# DemoSensorAddon.net
KiCad netlist of a schematic drawn in EAGLE
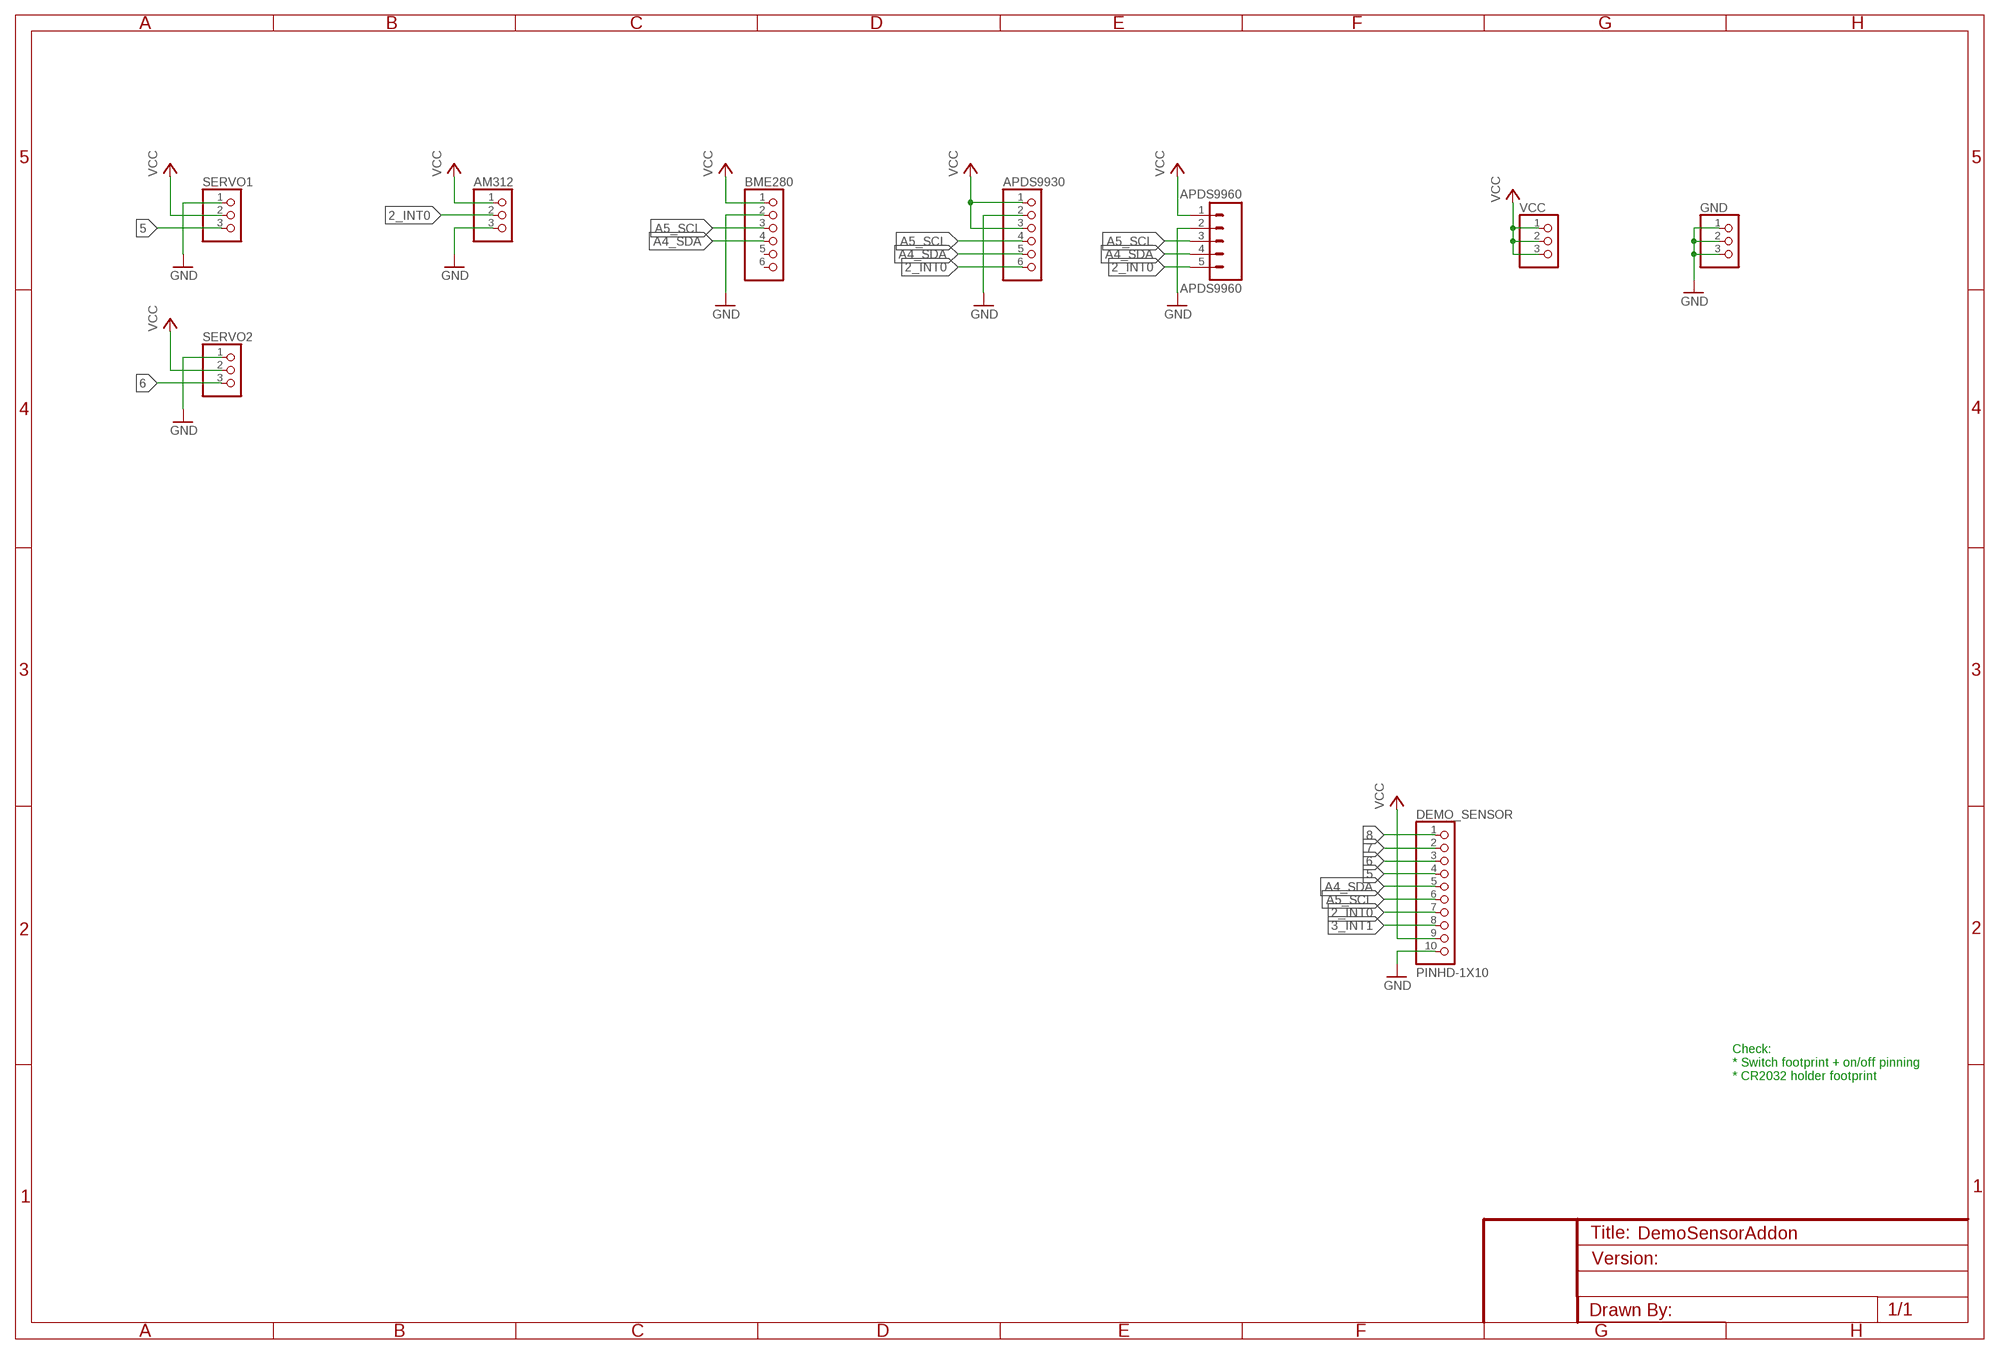
[diagram p0: schematic, sheet 1]

(export (version "E")
  (design (tool "Eeschema 10.0.6"))
  (components
    (comp (ref "AM312")
      (value "PINHD-1X3")
      (footprint "eagle-import:1X03")
      (libsource (lib "eagle-import") (part "PINHD-1X3"))
    )
    (comp (ref "APDS9930")
      (value "PINHD-1X6")
      (footprint "eagle-import:1X06")
      (libsource (lib "eagle-import") (part "PINHD-1X6"))
    )
    (comp (ref "APDS9960")
      (value "APDS9960")
      (footprint "eagle-import:1X05")
      (libsource (lib "eagle-import") (part "M05PTH"))
    )
    (comp (ref "BME280")
      (value "PINHD-1X6")
      (footprint "eagle-import:1X06")
      (libsource (lib "eagle-import") (part "PINHD-1X6"))
    )
    (comp (ref "DEMO_SENSOR")
      (value "PINHD-1X10")
      (footprint "eagle-import:1X10-BIG")
      (libsource (lib "eagle-import") (part "PINHD-1X10"))
    )
    (comp (ref "GND")
      (value "PINHD-1X3")
      (footprint "eagle-import:1X03")
      (libsource (lib "eagle-import") (part "PINHD-1X3"))
    )
    (comp (ref "SERVO1")
      (value "PINHD-1X3")
      (footprint "eagle-import:1X03")
      (libsource (lib "eagle-import") (part "PINHD-1X3"))
    )
    (comp (ref "SERVO2")
      (value "PINHD-1X3")
      (footprint "eagle-import:1X03")
      (libsource (lib "eagle-import") (part "PINHD-1X3"))
    )
    (comp (ref "VCC")
      (value "PINHD-1X3")
      (footprint "eagle-import:1X03")
      (libsource (lib "eagle-import") (part "PINHD-1X3"))
    )
  )
  (nets
    (net (code "1") (name "2_INT0") (class "Default")
      (node (ref "AM312") (pin "2") (pinfunction "2_2") (pintype "passive"))
      (node (ref "APDS9930") (pin "6") (pinfunction "6_6") (pintype "passive"))
      (node (ref "APDS9960") (pin "5") (pinfunction "5_5") (pintype "passive"))
      (node (ref "DEMO_SENSOR") (pin "7") (pinfunction "7_7") (pintype "passive"))
    )
    (net (code "2") (name "3_INT1") (class "Default")
      (node (ref "DEMO_SENSOR") (pin "8") (pinfunction "8_8") (pintype "passive"))
    )
    (net (code "3") (name "5") (class "Default")
      (node (ref "DEMO_SENSOR") (pin "4") (pinfunction "4_4") (pintype "passive"))
      (node (ref "SERVO1") (pin "3") (pinfunction "3_3") (pintype "passive"))
    )
    (net (code "4") (name "6") (class "Default")
      (node (ref "DEMO_SENSOR") (pin "3") (pinfunction "3_3") (pintype "passive"))
      (node (ref "SERVO2") (pin "3") (pinfunction "3_3") (pintype "passive"))
    )
    (net (code "5") (name "7") (class "Default")
      (node (ref "DEMO_SENSOR") (pin "2") (pinfunction "2_2") (pintype "passive"))
    )
    (net (code "6") (name "8") (class "Default")
      (node (ref "DEMO_SENSOR") (pin "1") (pinfunction "1_1") (pintype "passive"))
    )
    (net (code "7") (name "A4_SDA") (class "Default")
      (node (ref "APDS9930") (pin "5") (pinfunction "5_5") (pintype "passive"))
      (node (ref "APDS9960") (pin "4") (pinfunction "4_4") (pintype "passive"))
      (node (ref "BME280") (pin "4") (pinfunction "4_4") (pintype "passive"))
      (node (ref "DEMO_SENSOR") (pin "5") (pinfunction "5_5") (pintype "passive"))
    )
    (net (code "8") (name "A5_SCL") (class "Default")
      (node (ref "APDS9930") (pin "4") (pinfunction "4_4") (pintype "passive"))
      (node (ref "APDS9960") (pin "3") (pinfunction "3_3") (pintype "passive"))
      (node (ref "BME280") (pin "3") (pinfunction "3_3") (pintype "passive"))
      (node (ref "DEMO_SENSOR") (pin "6") (pinfunction "6_6") (pintype "passive"))
    )
    (net (code "9") (name "GND") (class "Default")
      (node (ref "AM312") (pin "3") (pinfunction "3_3") (pintype "passive"))
      (node (ref "APDS9930") (pin "2") (pinfunction "2_2") (pintype "passive"))
      (node (ref "APDS9960") (pin "2") (pinfunction "2_2") (pintype "passive"))
      (node (ref "BME280") (pin "2") (pinfunction "2_2") (pintype "passive"))
      (node (ref "DEMO_SENSOR") (pin "10") (pinfunction "10_10") (pintype "passive"))
      (node (ref "GND") (pin "1") (pinfunction "1_1") (pintype "passive"))
      (node (ref "GND") (pin "2") (pinfunction "2_2") (pintype "passive"))
      (node (ref "GND") (pin "3") (pinfunction "3_3") (pintype "passive"))
      (node (ref "SERVO1") (pin "1") (pinfunction "1_1") (pintype "passive"))
      (node (ref "SERVO2") (pin "1") (pinfunction "1_1") (pintype "passive"))
    )
    (net (code "10") (name "VCC") (class "Default")
      (node (ref "AM312") (pin "1") (pinfunction "1_1") (pintype "passive"))
      (node (ref "APDS9930") (pin "1") (pinfunction "1_1") (pintype "passive"))
      (node (ref "APDS9930") (pin "3") (pinfunction "3_3") (pintype "passive"))
      (node (ref "APDS9960") (pin "1") (pinfunction "1_1") (pintype "passive"))
      (node (ref "BME280") (pin "1") (pinfunction "1_1") (pintype "passive"))
      (node (ref "DEMO_SENSOR") (pin "9") (pinfunction "9_9") (pintype "passive"))
      (node (ref "SERVO1") (pin "2") (pinfunction "2_2") (pintype "passive"))
      (node (ref "SERVO2") (pin "2") (pinfunction "2_2") (pintype "passive"))
      (node (ref "VCC") (pin "1") (pinfunction "1_1") (pintype "passive"))
      (node (ref "VCC") (pin "2") (pinfunction "2_2") (pintype "passive"))
      (node (ref "VCC") (pin "3") (pinfunction "3_3") (pintype "passive"))
    )
    (net (code "11") (name "unconnected-(BME280-Pad5)") (class "Default")
      (node (ref "BME280") (pin "5") (pinfunction "5_5") (pintype "passive"))
    )
    (net (code "12") (name "unconnected-(BME280-Pad6)") (class "Default")
      (node (ref "BME280") (pin "6") (pinfunction "6_6") (pintype "passive"))
    )
  )
)
